# DC-DC-Brick.net
KiCad netlist of a schematic drawn in EAGLE
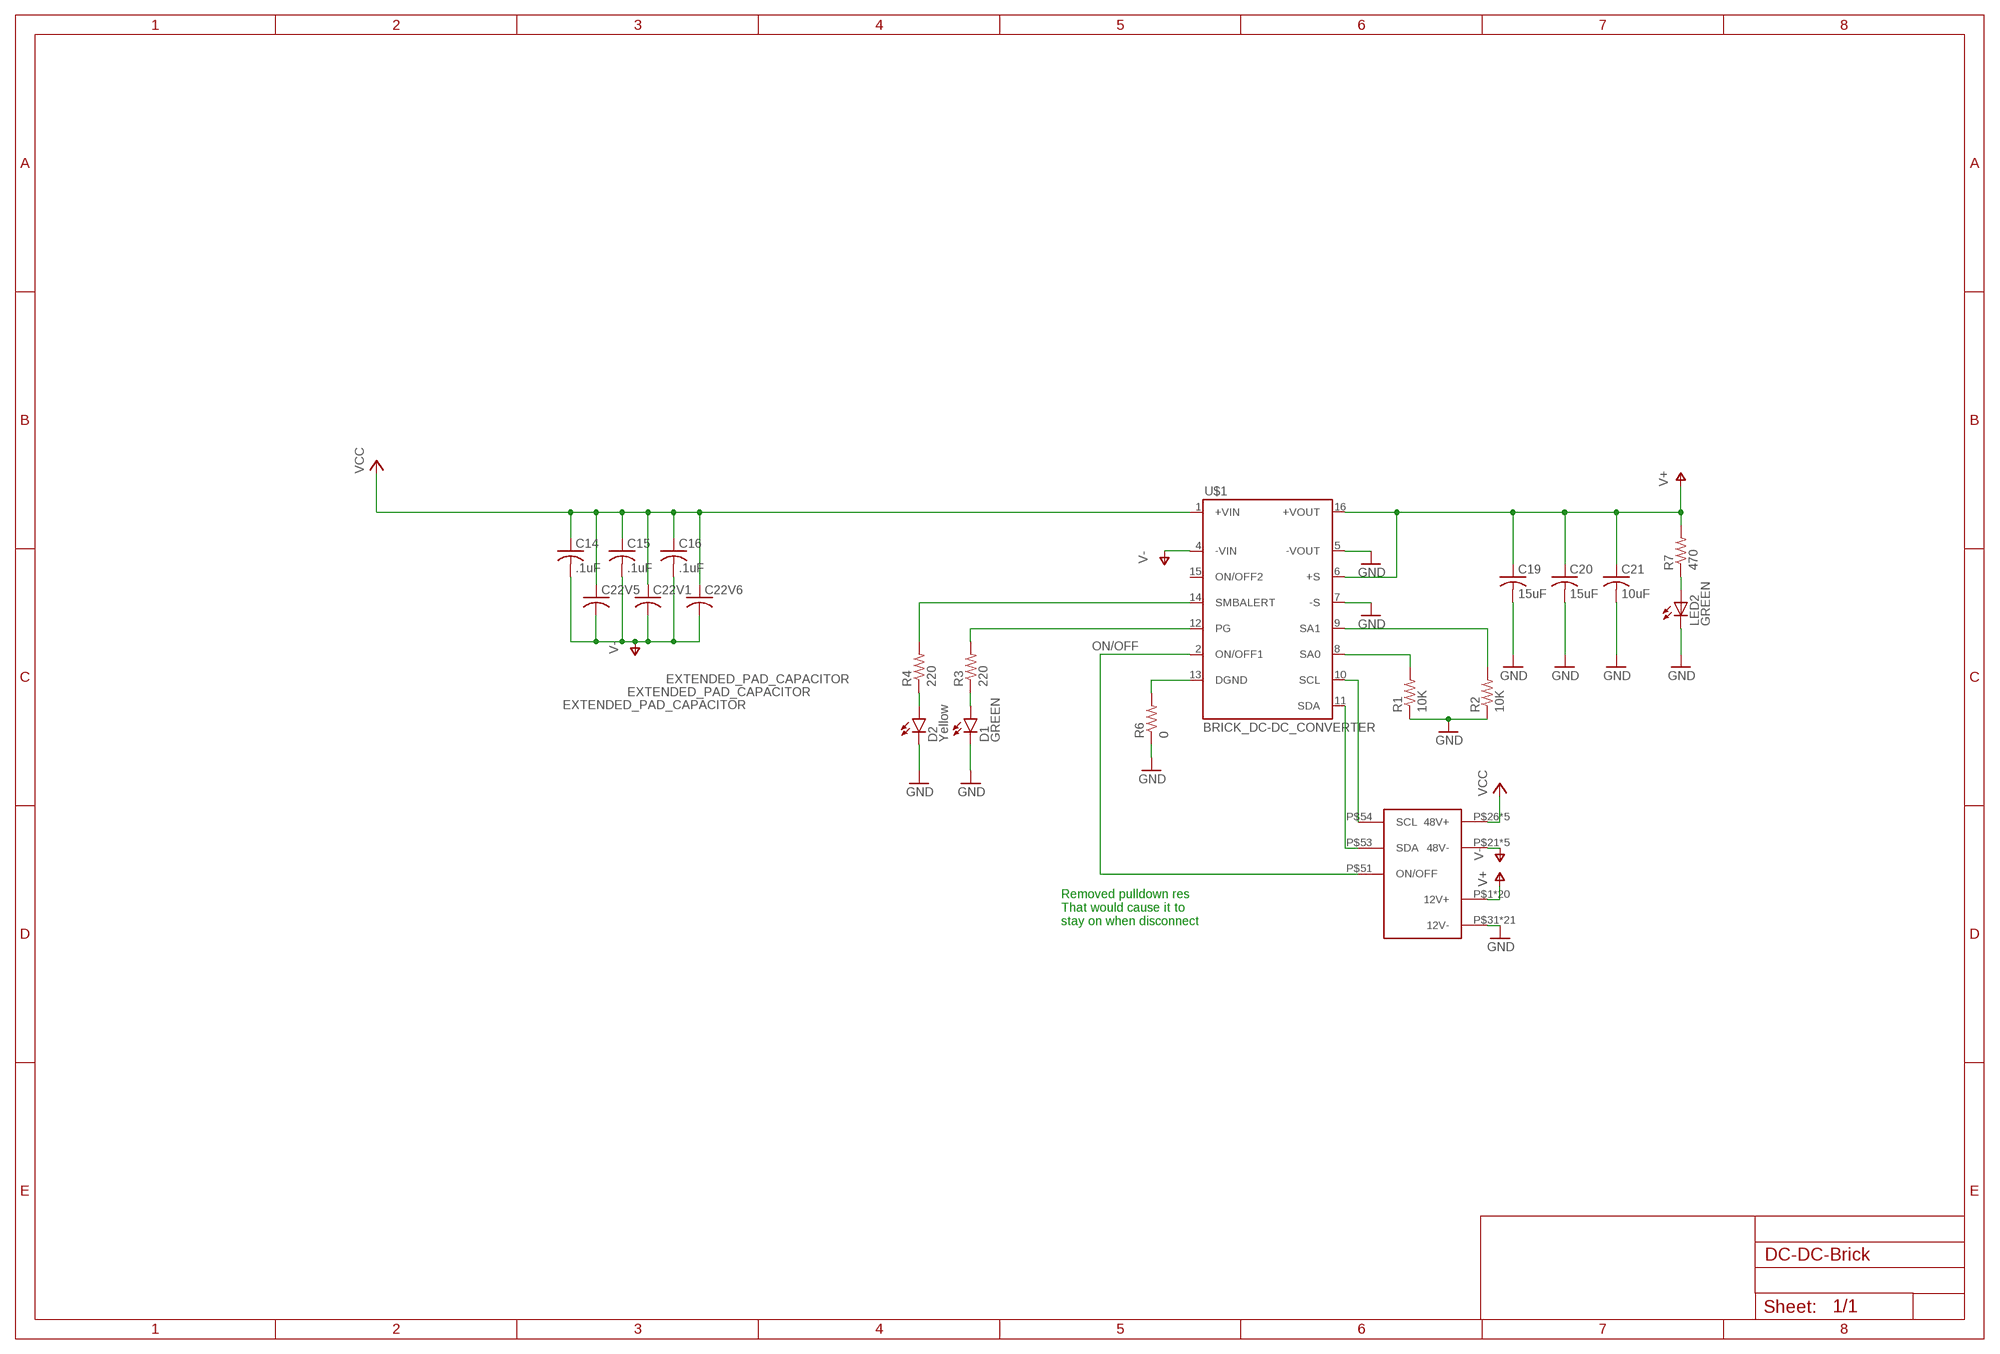
[diagram p0: schematic, sheet 1]

(export (version "E")
  (design (tool "Eeschema 10.0.6"))
  (components
    (comp (ref "C14")
      (value ".1uF")
      (footprint "eagle-import:C0603")
      (libsource (lib "eagle-import") (part "C-USC0603"))
    )
    (comp (ref "C15")
      (value ".1uF")
      (footprint "eagle-import:C0603")
      (libsource (lib "eagle-import") (part "C-USC0603"))
    )
    (comp (ref "C16")
      (value ".1uF")
      (footprint "eagle-import:C0603")
      (libsource (lib "eagle-import") (part "C-USC0603"))
    )
    (comp (ref "C19")
      (value "15uF")
      (footprint "eagle-import:C3216")
      (libsource (lib "eagle-import") (part "C-USC3216"))
    )
    (comp (ref "C20")
      (value "15uF")
      (footprint "eagle-import:C3216")
      (libsource (lib "eagle-import") (part "C-USC3216"))
    )
    (comp (ref "C21")
      (value "10uF")
      (footprint "eagle-import:C0603")
      (libsource (lib "eagle-import") (part "C-USC0603"))
    )
    (comp (ref "C22V1")
      (value "EXTENDED_PAD_CAPACITOR")
      (footprint "eagle-import:MODIFIED-NICHICON-UX-8X10")
      (libsource (lib "eagle-import") (part "EXTENDED_PAD_CAPACITOR"))
    )
    (comp (ref "C22V5")
      (value "EXTENDED_PAD_CAPACITOR")
      (footprint "eagle-import:MODIFIED-NICHICON-UX-8X10")
      (libsource (lib "eagle-import") (part "EXTENDED_PAD_CAPACITOR"))
    )
    (comp (ref "C22V6")
      (value "EXTENDED_PAD_CAPACITOR")
      (footprint "eagle-import:MODIFIED-NICHICON-UX-8X10")
      (libsource (lib "eagle-import") (part "EXTENDED_PAD_CAPACITOR"))
    )
    (comp (ref "D1")
      (value "GREEN")
      (footprint "eagle-import:LED-0603")
      (libsource (lib "eagle-import") (part "LED-GREEN0603"))
    )
    (comp (ref "D2")
      (value "Yellow")
      (footprint "eagle-import:LED-0603")
      (libsource (lib "eagle-import") (part "LED-YELLOW0603"))
    )
    (comp (ref "LED2")
      (value "GREEN")
      (footprint "eagle-import:LED-0603")
      (fields (field (name "PARTNO") "160-1446-1-ND"))
      (libsource (lib "eagle-import") (part "LED0603"))
    )
    (comp (ref "R1")
      (value "10K")
      (footprint "eagle-import:0603-RES")
      (libsource (lib "eagle-import") (part "10KOHM-1/10W-1%(0603)0603"))
    )
    (comp (ref "R2")
      (value "10K")
      (footprint "eagle-import:0603-RES")
      (libsource (lib "eagle-import") (part "10KOHM-1/10W-1%(0603)0603"))
    )
    (comp (ref "R3")
      (value "220")
      (footprint "eagle-import:0603-RES")
      (libsource (lib "eagle-import") (part "1KOHM-1/10W-1%(0603)"))
    )
    (comp (ref "R4")
      (value "220")
      (footprint "eagle-import:0603-RES")
      (libsource (lib "eagle-import") (part "1KOHM-1/10W-1%(0603)"))
    )
    (comp (ref "R6")
      (value "0")
      (footprint "eagle-import:0603-RES")
      (libsource (lib "eagle-import") (part "1KOHM-1/10W-1%(0603)"))
    )
    (comp (ref "R7")
      (value "470")
      (footprint "eagle-import:0603-RES")
      (libsource (lib "eagle-import") (part "470OHM1/10W1%(0603)"))
    )
    (comp (ref "U$1")
      (value "BRICK_DC-DC_CONVERTER")
      (footprint "eagle-import:BRICK_DC-DC_CONVERTER")
      (libsource (lib "eagle-import") (part "BRICK_DC-DC_CONVERTER"))
    )
    (comp (ref "U$3")
      (value "POWER-BRICK-CONNECTOR")
      (footprint "eagle-import:POWER-BRICK-CONNECTOR")
      (libsource (lib "eagle-import") (part "POWER-BRICK-CONNECTOR"))
    )
  )
  (nets
    (net (code "1") (name "/ON{slash}OFF") (class "Default")
      (node (ref "U$1") (pin "2") (pinfunction "ON/OFF1_2") (pintype "bidirectional"))
      (node (ref "U$3") (pin "P$51") (pinfunction "ON/OFF_P$51") (pintype "bidirectional"))
    )
    (net (code "2") (name "GND") (class "Default")
      (node (ref "C19") (pin "2") (pinfunction "2_2") (pintype "passive"))
      (node (ref "C20") (pin "2") (pinfunction "2_2") (pintype "passive"))
      (node (ref "C21") (pin "2") (pinfunction "2_2") (pintype "passive"))
      (node (ref "D1") (pin "C") (pinfunction "C_C") (pintype "passive"))
      (node (ref "D2") (pin "C") (pinfunction "C_C") (pintype "passive"))
      (node (ref "LED2") (pin "C") (pinfunction "C_C") (pintype "passive"))
      (node (ref "R1") (pin "1") (pinfunction "1_1") (pintype "passive"))
      (node (ref "R2") (pin "1") (pinfunction "1_1") (pintype "passive"))
      (node (ref "R6") (pin "1") (pinfunction "1_1") (pintype "passive"))
      (node (ref "U$1") (pin "5") (pinfunction "-VOUT_5") (pintype "power_in"))
      (node (ref "U$1") (pin "7") (pinfunction "-S_7") (pintype "bidirectional"))
      (node (ref "U$3") (pin "P$31") (pinfunction "12V-_P$31") (pintype "bidirectional"))
      (node (ref "U$3") (pin "P$32") (pinfunction "12V-_P$32") (pintype "bidirectional"))
      (node (ref "U$3") (pin "P$33") (pinfunction "12V-_P$33") (pintype "bidirectional"))
      (node (ref "U$3") (pin "P$34") (pinfunction "12V-_P$34") (pintype "bidirectional"))
      (node (ref "U$3") (pin "P$35") (pinfunction "12V-_P$35") (pintype "bidirectional"))
      (node (ref "U$3") (pin "P$36") (pinfunction "12V-_P$36") (pintype "bidirectional"))
      (node (ref "U$3") (pin "P$37") (pinfunction "12V-_P$37") (pintype "bidirectional"))
      (node (ref "U$3") (pin "P$38") (pinfunction "12V-_P$38") (pintype "bidirectional"))
      (node (ref "U$3") (pin "P$39") (pinfunction "12V-_P$39") (pintype "bidirectional"))
      (node (ref "U$3") (pin "P$40") (pinfunction "12V-_P$40") (pintype "bidirectional"))
      (node (ref "U$3") (pin "P$41") (pinfunction "12V-_P$41") (pintype "bidirectional"))
      (node (ref "U$3") (pin "P$42") (pinfunction "12V-_P$42") (pintype "bidirectional"))
      (node (ref "U$3") (pin "P$43") (pinfunction "12V-_P$43") (pintype "bidirectional"))
      (node (ref "U$3") (pin "P$44") (pinfunction "12V-_P$44") (pintype "bidirectional"))
      (node (ref "U$3") (pin "P$45") (pinfunction "12V-_P$45") (pintype "bidirectional"))
      (node (ref "U$3") (pin "P$46") (pinfunction "12V-_P$46") (pintype "bidirectional"))
      (node (ref "U$3") (pin "P$47") (pinfunction "12V-_P$47") (pintype "bidirectional"))
      (node (ref "U$3") (pin "P$48") (pinfunction "12V-_P$48") (pintype "bidirectional"))
      (node (ref "U$3") (pin "P$49") (pinfunction "12V-_P$49") (pintype "bidirectional"))
      (node (ref "U$3") (pin "P$50") (pinfunction "12V-_P$50") (pintype "bidirectional"))
      (node (ref "U$3") (pin "P$52") (pinfunction "12V-_P$52") (pintype "bidirectional"))
    )
    (net (code "3") (name "Net-(D1-PadA)") (class "Default")
      (node (ref "D1") (pin "A") (pinfunction "A_A") (pintype "passive"))
      (node (ref "R3") (pin "1") (pinfunction "1_1") (pintype "passive"))
    )
    (net (code "4") (name "Net-(D2-PadA)") (class "Default")
      (node (ref "D2") (pin "A") (pinfunction "A_A") (pintype "passive"))
      (node (ref "R4") (pin "1") (pinfunction "1_1") (pintype "passive"))
    )
    (net (code "5") (name "Net-(LED2-PadA)") (class "Default")
      (node (ref "LED2") (pin "A") (pinfunction "A_A") (pintype "passive"))
      (node (ref "R7") (pin "1") (pinfunction "1_1") (pintype "passive"))
    )
    (net (code "6") (name "Net-(U$1-DGND)") (class "Default")
      (node (ref "R6") (pin "2") (pinfunction "2_2") (pintype "passive"))
      (node (ref "U$1") (pin "13") (pinfunction "DGND_13") (pintype "power_in"))
    )
    (net (code "7") (name "Net-(U$1-PG)") (class "Default")
      (node (ref "R3") (pin "2") (pinfunction "2_2") (pintype "passive"))
      (node (ref "U$1") (pin "12") (pinfunction "PG_12") (pintype "bidirectional"))
    )
    (net (code "8") (name "Net-(U$1-SA0)") (class "Default")
      (node (ref "R1") (pin "2") (pinfunction "2_2") (pintype "passive"))
      (node (ref "U$1") (pin "8") (pinfunction "SA0_8") (pintype "bidirectional"))
    )
    (net (code "9") (name "Net-(U$1-SA1)") (class "Default")
      (node (ref "R2") (pin "2") (pinfunction "2_2") (pintype "passive"))
      (node (ref "U$1") (pin "9") (pinfunction "SA1_9") (pintype "bidirectional"))
    )
    (net (code "10") (name "Net-(U$1-SCL)") (class "Default")
      (node (ref "U$1") (pin "10") (pinfunction "SCL_10") (pintype "bidirectional"))
      (node (ref "U$3") (pin "P$54") (pinfunction "SCL_P$54") (pintype "bidirectional"))
    )
    (net (code "11") (name "Net-(U$1-SDA)") (class "Default")
      (node (ref "U$1") (pin "11") (pinfunction "SDA_11") (pintype "bidirectional"))
      (node (ref "U$3") (pin "P$53") (pinfunction "SDA_P$53") (pintype "bidirectional"))
    )
    (net (code "12") (name "Net-(U$1-SMBALERT)") (class "Default")
      (node (ref "R4") (pin "2") (pinfunction "2_2") (pintype "passive"))
      (node (ref "U$1") (pin "14") (pinfunction "SMBALERT_14") (pintype "bidirectional"))
    )
    (net (code "13") (name "V+") (class "Default")
      (node (ref "C19") (pin "1") (pinfunction "1_1") (pintype "passive"))
      (node (ref "C20") (pin "1") (pinfunction "1_1") (pintype "passive"))
      (node (ref "C21") (pin "1") (pinfunction "1_1") (pintype "passive"))
      (node (ref "R7") (pin "2") (pinfunction "2_2") (pintype "passive"))
      (node (ref "U$1") (pin "16") (pinfunction "+VOUT_16") (pintype "power_in"))
      (node (ref "U$1") (pin "6") (pinfunction "+S_6") (pintype "bidirectional"))
      (node (ref "U$3") (pin "P$1") (pinfunction "12V+_P$1") (pintype "bidirectional"))
      (node (ref "U$3") (pin "P$10") (pinfunction "12V+_P$10") (pintype "bidirectional"))
      (node (ref "U$3") (pin "P$11") (pinfunction "12V+_P$11") (pintype "bidirectional"))
      (node (ref "U$3") (pin "P$12") (pinfunction "12V+_P$12") (pintype "bidirectional"))
      (node (ref "U$3") (pin "P$13") (pinfunction "12V+_P$13") (pintype "bidirectional"))
      (node (ref "U$3") (pin "P$14") (pinfunction "12V+_P$14") (pintype "bidirectional"))
      (node (ref "U$3") (pin "P$15") (pinfunction "12V+_P$15") (pintype "bidirectional"))
      (node (ref "U$3") (pin "P$16") (pinfunction "12V+_P$16") (pintype "bidirectional"))
      (node (ref "U$3") (pin "P$17") (pinfunction "12V+_P$17") (pintype "bidirectional"))
      (node (ref "U$3") (pin "P$18") (pinfunction "12V+_P$18") (pintype "bidirectional"))
      (node (ref "U$3") (pin "P$19") (pinfunction "12V+_P$19") (pintype "bidirectional"))
      (node (ref "U$3") (pin "P$2") (pinfunction "12V+_P$2") (pintype "bidirectional"))
      (node (ref "U$3") (pin "P$20") (pinfunction "12V+_P$20") (pintype "bidirectional"))
      (node (ref "U$3") (pin "P$3") (pinfunction "12V+_P$3") (pintype "bidirectional"))
      (node (ref "U$3") (pin "P$4") (pinfunction "12V+_P$4") (pintype "bidirectional"))
      (node (ref "U$3") (pin "P$5") (pinfunction "12V+_P$5") (pintype "bidirectional"))
      (node (ref "U$3") (pin "P$6") (pinfunction "12V+_P$6") (pintype "bidirectional"))
      (node (ref "U$3") (pin "P$7") (pinfunction "12V+_P$7") (pintype "bidirectional"))
      (node (ref "U$3") (pin "P$8") (pinfunction "12V+_P$8") (pintype "bidirectional"))
      (node (ref "U$3") (pin "P$9") (pinfunction "12V+_P$9") (pintype "bidirectional"))
    )
    (net (code "14") (name "V-") (class "Default")
      (node (ref "C14") (pin "2") (pinfunction "2_2") (pintype "passive"))
      (node (ref "C15") (pin "2") (pinfunction "2_2") (pintype "passive"))
      (node (ref "C16") (pin "2") (pinfunction "2_2") (pintype "passive"))
      (node (ref "C22V1") (pin "P$1") (pinfunction "4_P$1") (pintype "passive"))
      (node (ref "C22V5") (pin "P$1") (pinfunction "4_P$1") (pintype "passive"))
      (node (ref "C22V6") (pin "P$1") (pinfunction "4_P$1") (pintype "passive"))
      (node (ref "U$1") (pin "4") (pinfunction "-VIN_4") (pintype "power_in"))
      (node (ref "U$3") (pin "P$21") (pinfunction "48V-_P$21") (pintype "bidirectional"))
      (node (ref "U$3") (pin "P$22") (pinfunction "48V-_P$22") (pintype "bidirectional"))
      (node (ref "U$3") (pin "P$23") (pinfunction "48V-_P$23") (pintype "bidirectional"))
      (node (ref "U$3") (pin "P$24") (pinfunction "48V-_P$24") (pintype "bidirectional"))
      (node (ref "U$3") (pin "P$25") (pinfunction "48V-_P$25") (pintype "bidirectional"))
    )
    (net (code "15") (name "VCC") (class "Default")
      (node (ref "C14") (pin "1") (pinfunction "1_1") (pintype "passive"))
      (node (ref "C15") (pin "1") (pinfunction "1_1") (pintype "passive"))
      (node (ref "C16") (pin "1") (pinfunction "1_1") (pintype "passive"))
      (node (ref "C22V1") (pin "P$3") (pinfunction "3_P$3") (pintype "passive"))
      (node (ref "C22V5") (pin "P$3") (pinfunction "3_P$3") (pintype "passive"))
      (node (ref "C22V6") (pin "P$3") (pinfunction "3_P$3") (pintype "passive"))
      (node (ref "U$1") (pin "1") (pinfunction "+VIN_1") (pintype "power_in"))
      (node (ref "U$3") (pin "P$26") (pinfunction "48V+_P$26") (pintype "bidirectional"))
      (node (ref "U$3") (pin "P$27") (pinfunction "48V+_P$27") (pintype "bidirectional"))
      (node (ref "U$3") (pin "P$28") (pinfunction "48V+_P$28") (pintype "bidirectional"))
      (node (ref "U$3") (pin "P$29") (pinfunction "48V+_P$29") (pintype "bidirectional"))
      (node (ref "U$3") (pin "P$30") (pinfunction "48V+_P$30") (pintype "bidirectional"))
    )
    (net (code "16") (name "unconnected-(U$1-ON{slash}OFF2-Pad15)") (class "Default")
      (node (ref "U$1") (pin "15") (pinfunction "ON/OFF2_15") (pintype "bidirectional"))
    )
  )
)
